# Small-BEC-5V.net
KiCad netlist of a schematic drawn in EAGLE
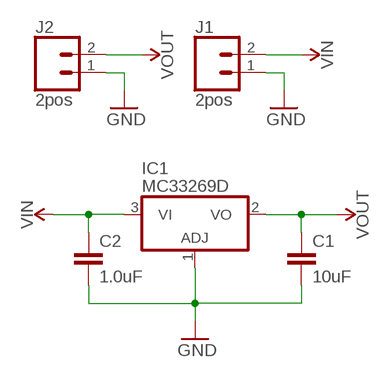
[diagram p0: schematic, sheet 1]

(export (version "E")
  (design (tool "Eeschema 10.0.6"))
  (components
    (comp (ref "C1")
      (value "10uF")
      (footprint "eagle-import:0805")
      (libsource (lib "eagle-import") (part "10UF-0805-10V-10%"))
    )
    (comp (ref "C2")
      (value "1.0uF")
      (footprint "eagle-import:0805")
      (libsource (lib "eagle-import") (part "1.0UF-0805-25V-10%"))
    )
    (comp (ref "IC1")
      (value "MC33269D")
      (footprint "eagle-import:DPACK")
      (libsource (lib "eagle-import") (part "MC33269?D"))
    )
    (comp (ref "J1")
      (value "2pos")
      (footprint "eagle-import:1X02")
      (libsource (lib "eagle-import") (part "CONN_02"))
    )
    (comp (ref "J2")
      (value "2pos")
      (footprint "eagle-import:1X02")
      (libsource (lib "eagle-import") (part "CONN_02"))
    )
  )
  (nets
    (net (code "1") (name "GND") (class "Default")
      (node (ref "C1") (pin "2") (pinfunction "2_2") (pintype "passive"))
      (node (ref "C2") (pin "2") (pinfunction "2_2") (pintype "passive"))
      (node (ref "IC1") (pin "1") (pinfunction "ADJ_1") (pintype "input"))
      (node (ref "J1") (pin "1") (pinfunction "1_1") (pintype "passive"))
      (node (ref "J2") (pin "1") (pinfunction "1_1") (pintype "passive"))
    )
    (net (code "2") (name "VIN") (class "Default")
      (node (ref "C2") (pin "1") (pinfunction "1_1") (pintype "passive"))
      (node (ref "IC1") (pin "3") (pinfunction "VI_3") (pintype "input"))
      (node (ref "J1") (pin "2") (pinfunction "2_2") (pintype "passive"))
    )
    (net (code "3") (name "VOUT") (class "Default")
      (node (ref "C1") (pin "1") (pinfunction "1_1") (pintype "passive"))
      (node (ref "IC1") (pin "2") (pinfunction "VO_2") (pintype "passive"))
      (node (ref "J2") (pin "2") (pinfunction "2_2") (pintype "passive"))
    )
  )
)
